# bleached.net
KiCad netlist of a schematic drawn in EAGLE
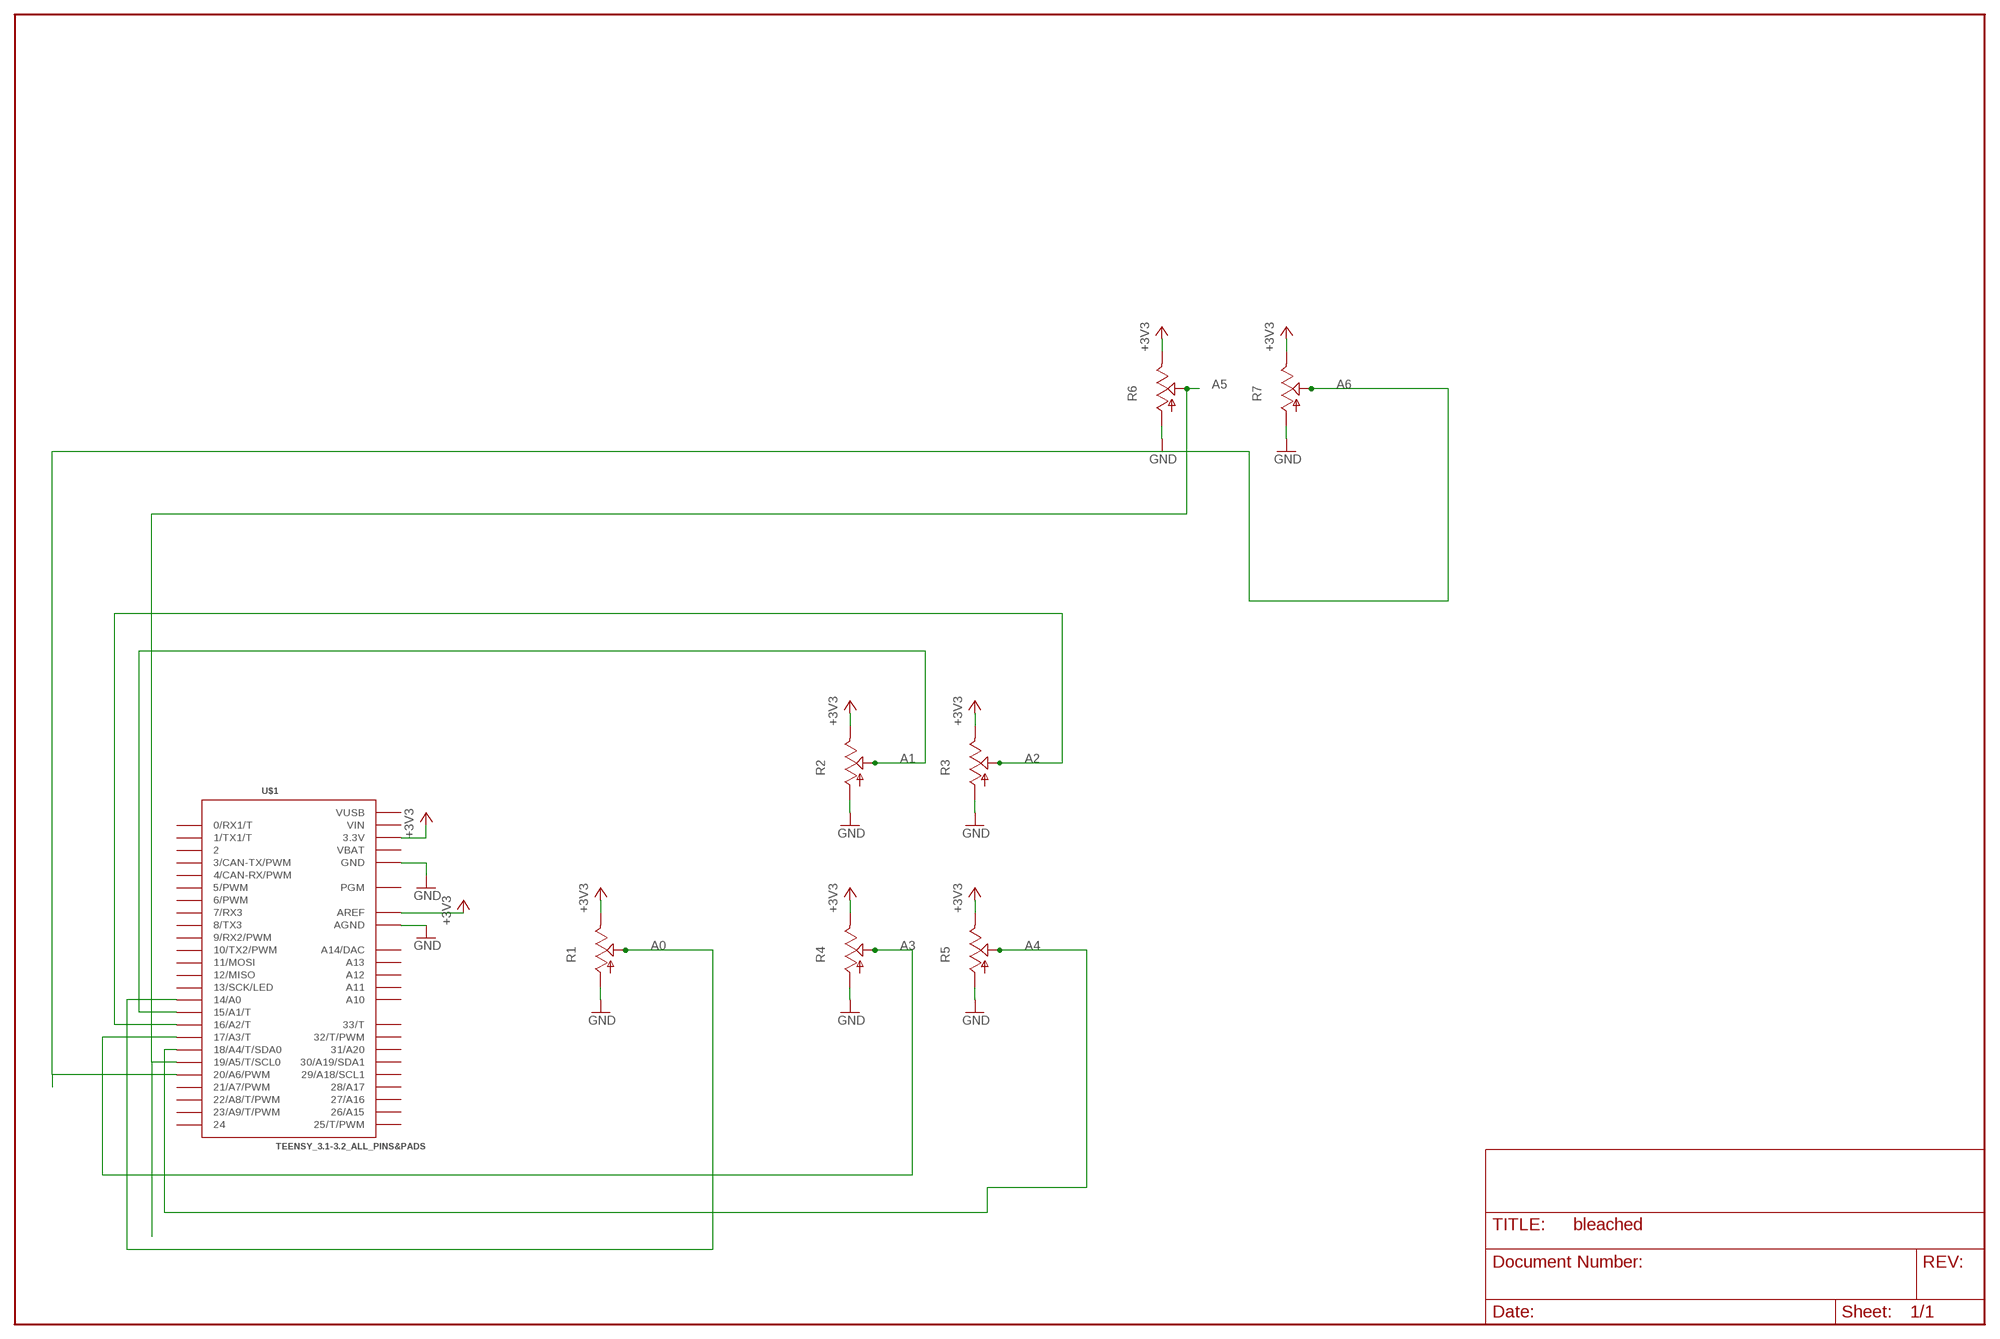
[diagram p0: schematic, sheet 1]

(export (version "E")
  (design (tool "Eeschema 10.0.6"))
  (components
    (comp (ref "R1")
      (value "SHAPES_POT-ALPS_POT_USVERTICAL_PS")
      (footprint "eagle-import:SHAPES_POT-ALPS_ALPS_POT_VERTICAL_PS")
      (libsource (lib "eagle-import") (part "SHAPES_POT-ALPS_POT_USVERTICAL_PS"))
    )
    (comp (ref "R2")
      (value "SHAPES_POT-ALPS_POT_USVERTICAL_PS")
      (footprint "eagle-import:SHAPES_POT-ALPS_ALPS_POT_VERTICAL_PS")
      (libsource (lib "eagle-import") (part "SHAPES_POT-ALPS_POT_USVERTICAL_PS"))
    )
    (comp (ref "R3")
      (value "SHAPES_POT-ALPS_POT_USVERTICAL_PS")
      (footprint "eagle-import:SHAPES_POT-ALPS_ALPS_POT_VERTICAL_PS")
      (libsource (lib "eagle-import") (part "SHAPES_POT-ALPS_POT_USVERTICAL_PS"))
    )
    (comp (ref "R4")
      (value "SHAPES_POT-ALPS_POT_USVERTICAL_PS")
      (footprint "eagle-import:SHAPES_POT-ALPS_ALPS_POT_VERTICAL_PS")
      (libsource (lib "eagle-import") (part "SHAPES_POT-ALPS_POT_USVERTICAL_PS"))
    )
    (comp (ref "R5")
      (value "SHAPES_POT-ALPS_POT_USVERTICAL_PS")
      (footprint "eagle-import:SHAPES_POT-ALPS_ALPS_POT_VERTICAL_PS")
      (libsource (lib "eagle-import") (part "SHAPES_POT-ALPS_POT_USVERTICAL_PS"))
    )
    (comp (ref "R6")
      (value "SHAPES_POT-ALPS_POT_USVERTICAL_PS")
      (footprint "eagle-import:SHAPES_POT-ALPS_ALPS_POT_VERTICAL_PS")
      (libsource (lib "eagle-import") (part "SHAPES_POT-ALPS_POT_USVERTICAL_PS"))
    )
    (comp (ref "R7")
      (value "SHAPES_POT-ALPS_POT_USVERTICAL_PS")
      (footprint "eagle-import:SHAPES_POT-ALPS_ALPS_POT_VERTICAL_PS")
      (libsource (lib "eagle-import") (part "SHAPES_POT-ALPS_POT_USVERTICAL_PS"))
    )
    (comp (ref "U$1")
      (value "TEENSY_3.1-3.2_ALL_PINS&PADS")
      (footprint "eagle-import:TEENSY_3.0-3.2_ALL_PINS_&_PADS")
      (libsource (lib "eagle-import") (part "TEENSY_3.1-3.2_ALL_PINS&PADS"))
    )
  )
  (nets
    (net (code "1") (name "+3V3") (class "Default")
      (node (ref "R1") (pin "P$1") (pinfunction "E_P$1") (pintype "passive"))
      (node (ref "R2") (pin "P$1") (pinfunction "E_P$1") (pintype "passive"))
      (node (ref "R3") (pin "P$1") (pinfunction "E_P$1") (pintype "passive"))
      (node (ref "R4") (pin "P$1") (pinfunction "E_P$1") (pintype "passive"))
      (node (ref "R5") (pin "P$1") (pinfunction "E_P$1") (pintype "passive"))
      (node (ref "R6") (pin "P$1") (pinfunction "E_P$1") (pintype "passive"))
      (node (ref "R7") (pin "P$1") (pinfunction "E_P$1") (pintype "passive"))
      (node (ref "U$1") (pin "3.3V") (pinfunction "3.3V_3.3V") (pintype "power_in"))
      (node (ref "U$1") (pin "3.3V1") (pinfunction "3.3V_3.3V1") (pintype "power_in"))
      (node (ref "U$1") (pin "3.3V2") (pinfunction "3.3V_3.3V2") (pintype "power_in"))
      (node (ref "U$1") (pin "AREF") (pinfunction "AREF_AREF") (pintype "power_in"))
    )
    (net (code "2") (name "/A0") (class "Default")
      (node (ref "R1") (pin "P$2") (pinfunction "S_P$2") (pintype "passive"))
      (node (ref "U$1") (pin "14/A0") (pinfunction "14/A0_14/A0") (pintype "bidirectional"))
    )
    (net (code "3") (name "/A1") (class "Default")
      (node (ref "R2") (pin "P$2") (pinfunction "S_P$2") (pintype "passive"))
      (node (ref "U$1") (pin "15/A1") (pinfunction "15/A1/T_15/A1") (pintype "bidirectional"))
    )
    (net (code "4") (name "/A2") (class "Default")
      (node (ref "R3") (pin "P$2") (pinfunction "S_P$2") (pintype "passive"))
      (node (ref "U$1") (pin "16/A2") (pinfunction "16/A2/T_16/A2") (pintype "bidirectional"))
    )
    (net (code "5") (name "/A3") (class "Default")
      (node (ref "R4") (pin "P$2") (pinfunction "S_P$2") (pintype "passive"))
      (node (ref "U$1") (pin "17/A3") (pinfunction "17/A3/T_17/A3") (pintype "bidirectional"))
    )
    (net (code "6") (name "/A4") (class "Default")
      (node (ref "R5") (pin "P$2") (pinfunction "S_P$2") (pintype "passive"))
      (node (ref "U$1") (pin "18/A4") (pinfunction "18/A4/T/SDA0_18/A4") (pintype "bidirectional"))
    )
    (net (code "7") (name "/A5") (class "Default")
      (node (ref "R6") (pin "P$2") (pinfunction "S_P$2") (pintype "passive"))
      (node (ref "U$1") (pin "19/A5") (pinfunction "19/A5/T/SCL0_19/A5") (pintype "bidirectional"))
    )
    (net (code "8") (name "/A6") (class "Default")
      (node (ref "R7") (pin "P$2") (pinfunction "S_P$2") (pintype "passive"))
      (node (ref "U$1") (pin "20/A6") (pinfunction "20/A6/PWM_20/A6") (pintype "bidirectional"))
    )
    (net (code "9") (name "/VBAT") (class "Default")
      (node (ref "U$1") (pin "VBAT") (pinfunction "VBAT_VBAT") (pintype "power_in"))
    )
    (net (code "10") (name "/VIN") (class "Default")
      (node (ref "U$1") (pin "VIN") (pinfunction "VIN_VIN") (pintype "power_in"))
    )
    (net (code "11") (name "/VUSB") (class "Default")
      (node (ref "U$1") (pin "VUSB") (pinfunction "VUSB_VUSB") (pintype "power_in"))
    )
    (net (code "12") (name "GND") (class "Default")
      (node (ref "R1") (pin "P$3") (pinfunction "A_P$3") (pintype "passive"))
      (node (ref "R2") (pin "P$3") (pinfunction "A_P$3") (pintype "passive"))
      (node (ref "R3") (pin "P$3") (pinfunction "A_P$3") (pintype "passive"))
      (node (ref "R4") (pin "P$3") (pinfunction "A_P$3") (pintype "passive"))
      (node (ref "R5") (pin "P$3") (pinfunction "A_P$3") (pintype "passive"))
      (node (ref "R6") (pin "P$3") (pinfunction "A_P$3") (pintype "passive"))
      (node (ref "R7") (pin "P$3") (pinfunction "A_P$3") (pintype "passive"))
      (node (ref "U$1") (pin "AGND") (pinfunction "AGND_AGND") (pintype "power_in"))
      (node (ref "U$1") (pin "GND") (pinfunction "GND_GND") (pintype "power_in"))
      (node (ref "U$1") (pin "GND1") (pinfunction "GND_GND1") (pintype "power_in"))
      (node (ref "U$1") (pin "GND2") (pinfunction "GND_GND2") (pintype "power_in"))
    )
    (net (code "13") (name "unconnected-(U$1-0{slash}RX1{slash}T-Pad0)") (class "Default")
      (node (ref "U$1") (pin "0") (pinfunction "0/RX1/T_0") (pintype "bidirectional"))
    )
    (net (code "14") (name "unconnected-(U$1-1{slash}TX1{slash}T-Pad1)") (class "Default")
      (node (ref "U$1") (pin "1") (pinfunction "1/TX1/T_1") (pintype "bidirectional"))
    )
    (net (code "15") (name "unconnected-(U$1-3{slash}CAN-TX{slash}PWM-Pad3)") (class "Default")
      (node (ref "U$1") (pin "3") (pinfunction "3/CAN-TX/PWM_3") (pintype "bidirectional"))
    )
    (net (code "16") (name "unconnected-(U$1-4{slash}CAN-RX{slash}PWM-Pad4)") (class "Default")
      (node (ref "U$1") (pin "4") (pinfunction "4/CAN-RX/PWM_4") (pintype "bidirectional"))
    )
    (net (code "17") (name "unconnected-(U$1-5{slash}PWM-Pad5)") (class "Default")
      (node (ref "U$1") (pin "5") (pinfunction "5/PWM_5") (pintype "bidirectional"))
    )
    (net (code "18") (name "unconnected-(U$1-6{slash}PWM-Pad6)") (class "Default")
      (node (ref "U$1") (pin "6") (pinfunction "6/PWM_6") (pintype "bidirectional"))
    )
    (net (code "19") (name "unconnected-(U$1-7{slash}RX3-Pad7)") (class "Default")
      (node (ref "U$1") (pin "7") (pinfunction "7/RX3_7") (pintype "bidirectional"))
    )
    (net (code "20") (name "unconnected-(U$1-8{slash}TX3-Pad8)") (class "Default")
      (node (ref "U$1") (pin "8") (pinfunction "8/TX3_8") (pintype "bidirectional"))
    )
    (net (code "21") (name "unconnected-(U$1-9{slash}RX2{slash}PWM-Pad9)") (class "Default")
      (node (ref "U$1") (pin "9") (pinfunction "9/RX2/PWM_9") (pintype "bidirectional"))
    )
    (net (code "22") (name "unconnected-(U$1-10{slash}TX2{slash}PWM-Pad10)") (class "Default")
      (node (ref "U$1") (pin "10") (pinfunction "10/TX2/PWM_10") (pintype "bidirectional"))
    )
    (net (code "23") (name "unconnected-(U$1-11{slash}MOSI-Pad11)") (class "Default")
      (node (ref "U$1") (pin "11") (pinfunction "11/MOSI_11") (pintype "bidirectional"))
    )
    (net (code "24") (name "unconnected-(U$1-12{slash}MISO-Pad12)") (class "Default")
      (node (ref "U$1") (pin "12") (pinfunction "12/MISO_12") (pintype "bidirectional"))
    )
    (net (code "25") (name "unconnected-(U$1-13{slash}SCK{slash}LED-Pad13)") (class "Default")
      (node (ref "U$1") (pin "13") (pinfunction "13/SCK/LED_13") (pintype "bidirectional"))
    )
    (net (code "26") (name "unconnected-(U$1-21{slash}A7{slash}PWM-Pad21{slash}A7)") (class "Default")
      (node (ref "U$1") (pin "21/A7") (pinfunction "21/A7/PWM_21/A7") (pintype "bidirectional"))
    )
    (net (code "27") (name "unconnected-(U$1-22{slash}A8{slash}T{slash}PWM-Pad22{slash}A8)") (class "Default")
      (node (ref "U$1") (pin "22/A8") (pinfunction "22/A8/T/PWM_22/A8") (pintype "bidirectional"))
    )
    (net (code "28") (name "unconnected-(U$1-23{slash}A9{slash}T{slash}PWM-Pad23{slash}A9)") (class "Default")
      (node (ref "U$1") (pin "23/A9") (pinfunction "23/A9/T/PWM_23/A9") (pintype "bidirectional"))
    )
    (net (code "29") (name "unconnected-(U$1-25{slash}T{slash}PWM-Pad25)") (class "Default")
      (node (ref "U$1") (pin "25") (pinfunction "25/T/PWM_25") (pintype "bidirectional"))
    )
    (net (code "30") (name "unconnected-(U$1-26{slash}A15-Pad26)") (class "Default")
      (node (ref "U$1") (pin "26") (pinfunction "26/A15_26") (pintype "bidirectional"))
    )
    (net (code "31") (name "unconnected-(U$1-27{slash}A16-Pad27)") (class "Default")
      (node (ref "U$1") (pin "27") (pinfunction "27/A16_27") (pintype "bidirectional"))
    )
    (net (code "32") (name "unconnected-(U$1-28{slash}A17-Pad28)") (class "Default")
      (node (ref "U$1") (pin "28") (pinfunction "28/A17_28") (pintype "bidirectional"))
    )
    (net (code "33") (name "unconnected-(U$1-29{slash}A18{slash}SCL1-Pad29)") (class "Default")
      (node (ref "U$1") (pin "29") (pinfunction "29/A18/SCL1_29") (pintype "bidirectional"))
    )
    (net (code "34") (name "unconnected-(U$1-30{slash}A19{slash}SDA1-Pad30)") (class "Default")
      (node (ref "U$1") (pin "30") (pinfunction "30/A19/SDA1_30") (pintype "bidirectional"))
    )
    (net (code "35") (name "unconnected-(U$1-31{slash}A20-Pad31)") (class "Default")
      (node (ref "U$1") (pin "31") (pinfunction "31/A20_31") (pintype "bidirectional"))
    )
    (net (code "36") (name "unconnected-(U$1-32{slash}T{slash}PWM-Pad32)") (class "Default")
      (node (ref "U$1") (pin "32") (pinfunction "32/T/PWM_32") (pintype "bidirectional"))
    )
    (net (code "37") (name "unconnected-(U$1-33{slash}T-Pad33)") (class "Default")
      (node (ref "U$1") (pin "33") (pinfunction "33/T_33") (pintype "bidirectional"))
    )
    (net (code "38") (name "unconnected-(U$1-A14{slash}DAC-PadRESET{slash}DAC)") (class "Default")
      (node (ref "U$1") (pin "RESET/DAC") (pinfunction "A14/DAC_RESET/DAC") (pintype "bidirectional"))
    )
    (net (code "39") (name "unconnected-(U$1-Pad2)") (class "Default")
      (node (ref "U$1") (pin "2") (pinfunction "2_2") (pintype "bidirectional"))
    )
    (net (code "40") (name "unconnected-(U$1-Pad24)") (class "Default")
      (node (ref "U$1") (pin "24") (pinfunction "24_24") (pintype "bidirectional"))
    )
    (net (code "41") (name "unconnected-(U$1-PadA10)") (class "Default")
      (node (ref "U$1") (pin "A10") (pinfunction "A10_A10") (pintype "bidirectional"))
    )
    (net (code "42") (name "unconnected-(U$1-PadA11)") (class "Default")
      (node (ref "U$1") (pin "A11") (pinfunction "A11_A11") (pintype "bidirectional"))
    )
    (net (code "43") (name "unconnected-(U$1-PadA12)") (class "Default")
      (node (ref "U$1") (pin "A12") (pinfunction "A12_A12") (pintype "bidirectional"))
    )
    (net (code "44") (name "unconnected-(U$1-PadA13)") (class "Default")
      (node (ref "U$1") (pin "A13") (pinfunction "A13_A13") (pintype "bidirectional"))
    )
    (net (code "45") (name "unconnected-(U$1-PadPGM)") (class "Default")
      (node (ref "U$1") (pin "PGM") (pinfunction "PGM_PGM") (pintype "bidirectional"))
    )
  )
)
